# amp1_v0001.net
KiCad netlist of a schematic drawn in EAGLE
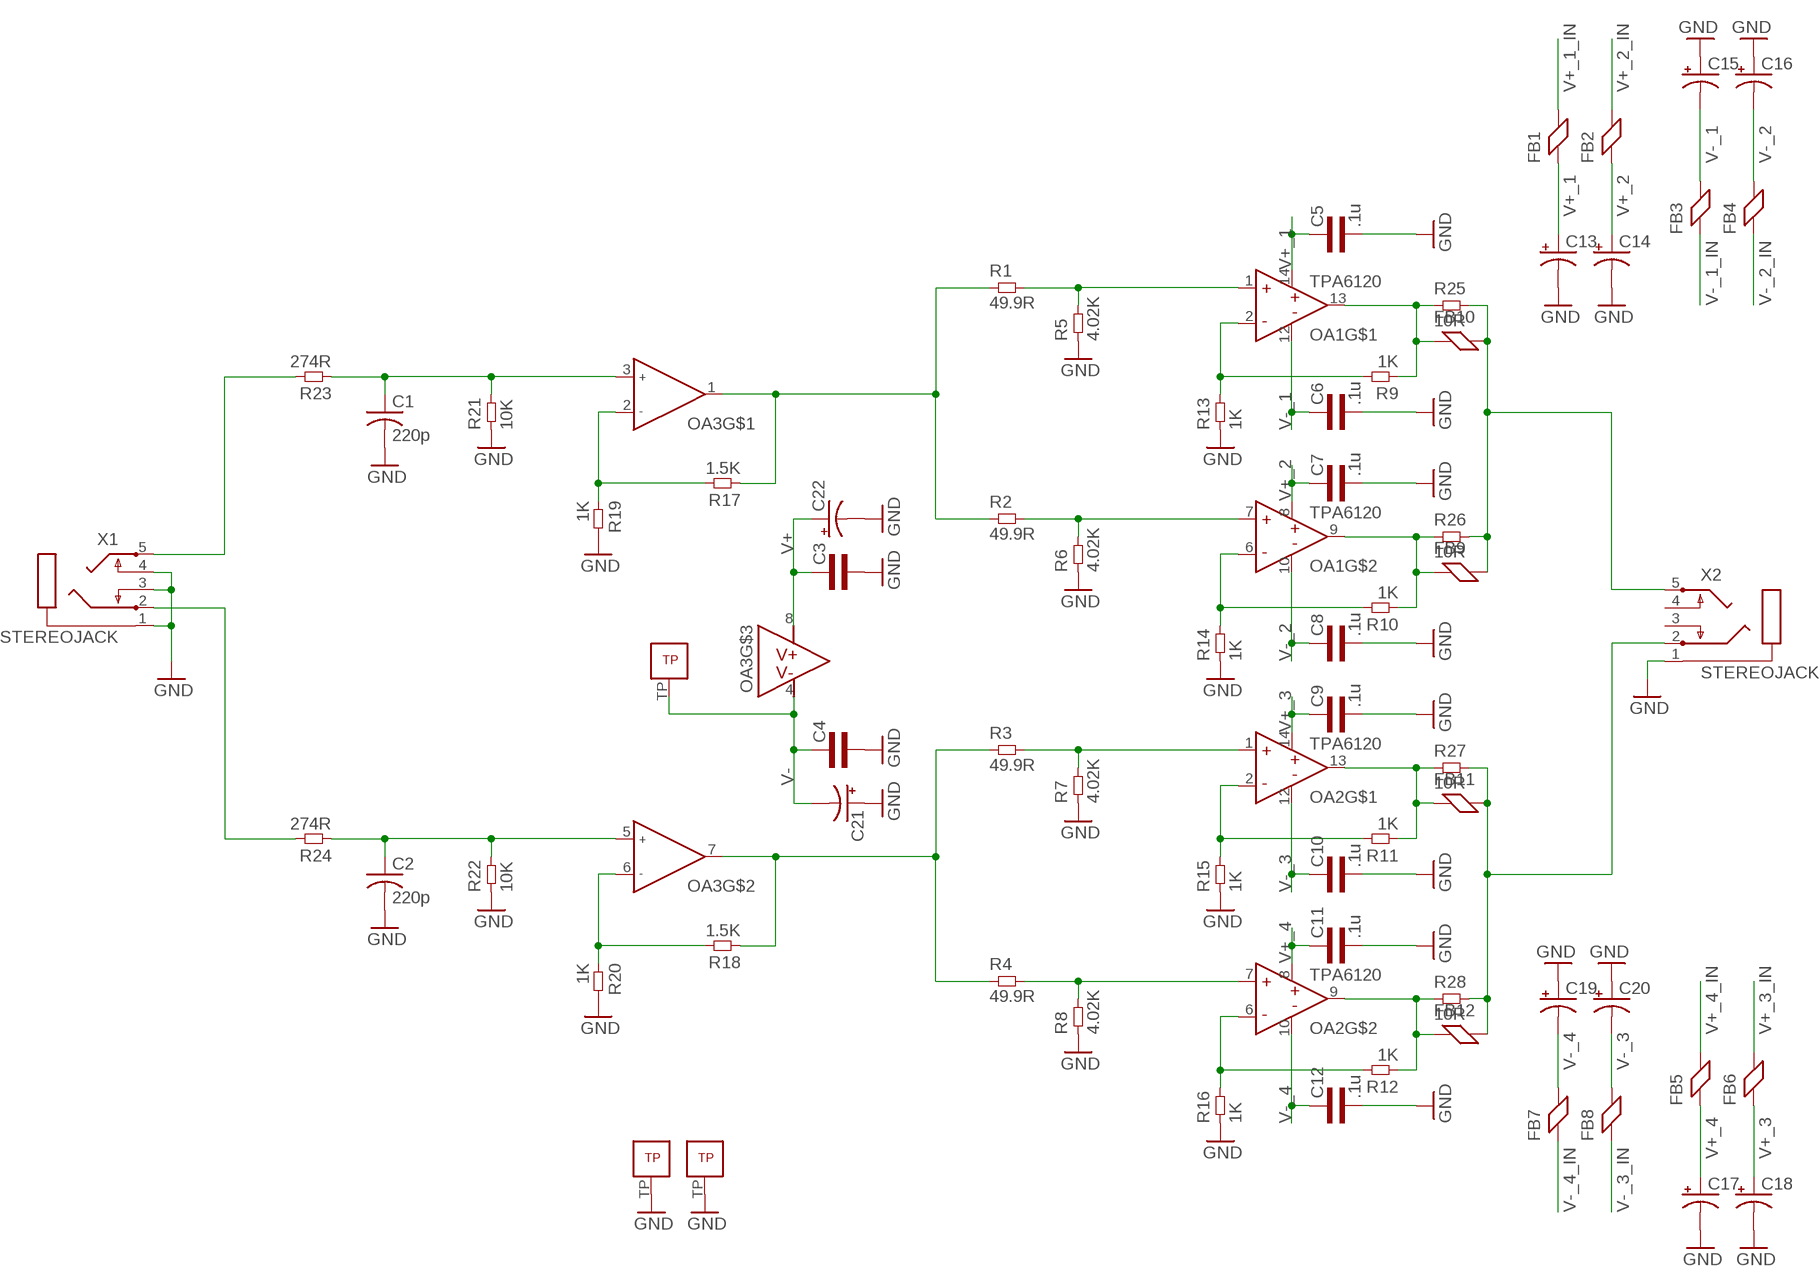
[diagram p0: schematic, sheet 1]

(export (version "E")
  (design (tool "Eeschema 10.0.6"))
  (components
    (comp (ref "C1")
      (value "220p")
      (footprint "eagle-import:C025-025X050")
      (libsource (lib "eagle-import") (part "C-US025-025X050"))
    )
    (comp (ref "C2")
      (value "220p")
      (footprint "eagle-import:C025-025X050")
      (libsource (lib "eagle-import") (part "C-US025-025X050"))
    )
    (comp (ref "C3")
      (value "CAP0603L3")
      (footprint "eagle-import:0603L3")
      (libsource (lib "eagle-import") (part "CAP0603L3"))
    )
    (comp (ref "C4")
      (value "CAP0603L3")
      (footprint "eagle-import:0603L3")
      (libsource (lib "eagle-import") (part "CAP0603L3"))
    )
    (comp (ref "C5")
      (value ".1u")
      (footprint "eagle-import:0603L3")
      (libsource (lib "eagle-import") (part "CAP0603L3"))
    )
    (comp (ref "C6")
      (value ".1u")
      (footprint "eagle-import:0603L3")
      (libsource (lib "eagle-import") (part "CAP0603L3"))
    )
    (comp (ref "C7")
      (value ".1u")
      (footprint "eagle-import:0603L3")
      (libsource (lib "eagle-import") (part "CAP0603L3"))
    )
    (comp (ref "C8")
      (value ".1u")
      (footprint "eagle-import:0603L3")
      (libsource (lib "eagle-import") (part "CAP0603L3"))
    )
    (comp (ref "C9")
      (value ".1u")
      (footprint "eagle-import:0603L3")
      (libsource (lib "eagle-import") (part "CAP0603L3"))
    )
    (comp (ref "C10")
      (value ".1u")
      (footprint "eagle-import:0603L3")
      (libsource (lib "eagle-import") (part "CAP0603L3"))
    )
    (comp (ref "C11")
      (value ".1u")
      (footprint "eagle-import:0603L3")
      (libsource (lib "eagle-import") (part "CAP0603L3"))
    )
    (comp (ref "C12")
      (value ".1u")
      (footprint "eagle-import:0603L3")
      (libsource (lib "eagle-import") (part "CAP0603L3"))
    )
    (comp (ref "C13")
      (value "CPOL-USE2-5")
      (footprint "eagle-import:E2-5")
      (libsource (lib "eagle-import") (part "CPOL-USE2-5"))
    )
    (comp (ref "C14")
      (value "CPOL-USE2-5")
      (footprint "eagle-import:E2-5")
      (libsource (lib "eagle-import") (part "CPOL-USE2-5"))
    )
    (comp (ref "C15")
      (value "CPOL-USE2-5")
      (footprint "eagle-import:E2-5")
      (libsource (lib "eagle-import") (part "CPOL-USE2-5"))
    )
    (comp (ref "C16")
      (value "CPOL-USE2-5")
      (footprint "eagle-import:E2-5")
      (libsource (lib "eagle-import") (part "CPOL-USE2-5"))
    )
    (comp (ref "C17")
      (value "CPOL-USE2-5")
      (footprint "eagle-import:E2-5")
      (libsource (lib "eagle-import") (part "CPOL-USE2-5"))
    )
    (comp (ref "C18")
      (value "CPOL-USE2-5")
      (footprint "eagle-import:E2-5")
      (libsource (lib "eagle-import") (part "CPOL-USE2-5"))
    )
    (comp (ref "C19")
      (value "CPOL-USE2-5")
      (footprint "eagle-import:E2-5")
      (libsource (lib "eagle-import") (part "CPOL-USE2-5"))
    )
    (comp (ref "C20")
      (value "CPOL-USE2-5")
      (footprint "eagle-import:E2-5")
      (libsource (lib "eagle-import") (part "CPOL-USE2-5"))
    )
    (comp (ref "C21")
      (value "CPOL-USE2-5")
      (footprint "eagle-import:E2-5")
      (libsource (lib "eagle-import") (part "CPOL-USE2-5"))
    )
    (comp (ref "C22")
      (value "CPOL-USE2-5")
      (footprint "eagle-import:E2-5")
      (libsource (lib "eagle-import") (part "CPOL-USE2-5"))
    )
    (comp (ref "FB1")
      (value "FERRITE0805L3")
      (footprint "eagle-import:0805L3")
      (libsource (lib "eagle-import") (part "FERRITE0805L3"))
    )
    (comp (ref "FB2")
      (value "FERRITE0805L3")
      (footprint "eagle-import:0805L3")
      (libsource (lib "eagle-import") (part "FERRITE0805L3"))
    )
    (comp (ref "FB3")
      (value "FERRITE0805L3")
      (footprint "eagle-import:0805L3")
      (libsource (lib "eagle-import") (part "FERRITE0805L3"))
    )
    (comp (ref "FB4")
      (value "FERRITE0805L3")
      (footprint "eagle-import:0805L3")
      (libsource (lib "eagle-import") (part "FERRITE0805L3"))
    )
    (comp (ref "FB5")
      (value "FERRITE0805L3")
      (footprint "eagle-import:0805L3")
      (libsource (lib "eagle-import") (part "FERRITE0805L3"))
    )
    (comp (ref "FB6")
      (value "FERRITE0805L3")
      (footprint "eagle-import:0805L3")
      (libsource (lib "eagle-import") (part "FERRITE0805L3"))
    )
    (comp (ref "FB7")
      (value "FERRITE0805L3")
      (footprint "eagle-import:0805L3")
      (libsource (lib "eagle-import") (part "FERRITE0805L3"))
    )
    (comp (ref "FB8")
      (value "FERRITE0805L3")
      (footprint "eagle-import:0805L3")
      (libsource (lib "eagle-import") (part "FERRITE0805L3"))
    )
    (comp (ref "FB9")
      (value "FERRITE0805L3")
      (footprint "eagle-import:0805L3")
      (libsource (lib "eagle-import") (part "FERRITE0805L3"))
    )
    (comp (ref "FB10")
      (value "FERRITE0805L3")
      (footprint "eagle-import:0805L3")
      (libsource (lib "eagle-import") (part "FERRITE0805L3"))
    )
    (comp (ref "FB11")
      (value "FERRITE0805L3")
      (footprint "eagle-import:0805L3")
      (libsource (lib "eagle-import") (part "FERRITE0805L3"))
    )
    (comp (ref "FB12")
      (value "FERRITE0805L3")
      (footprint "eagle-import:0805L3")
      (libsource (lib "eagle-import") (part "FERRITE0805L3"))
    )
    (comp (ref "OA1")
      (value "TPA6120QFN")
      (footprint "eagle-import:S-PVQFN-N14")
      (libsource (lib "eagle-import") (part "TPA6120QFN"))
    )
    (comp (ref "OA2")
      (value "TPA6120QFN")
      (footprint "eagle-import:S-PVQFN-N14")
      (libsource (lib "eagle-import") (part "TPA6120QFN"))
    )
    (comp (ref "OA3")
      (value "OPA1612")
      (footprint "eagle-import:S-PWSON-N8")
      (libsource (lib "eagle-import") (part "OPA1612"))
    )
    (comp (ref "R1")
      (value "49.9R")
      (footprint "eagle-import:0805L3")
      (libsource (lib "eagle-import") (part "RES0805L3"))
    )
    (comp (ref "R2")
      (value "49.9R")
      (footprint "eagle-import:0805L3")
      (libsource (lib "eagle-import") (part "RES0805L3"))
    )
    (comp (ref "R3")
      (value "49.9R")
      (footprint "eagle-import:0805L3")
      (libsource (lib "eagle-import") (part "RES0805L3"))
    )
    (comp (ref "R4")
      (value "49.9R")
      (footprint "eagle-import:0805L3")
      (libsource (lib "eagle-import") (part "RES0805L3"))
    )
    (comp (ref "R5")
      (value "4.02K")
      (footprint "eagle-import:0805L3")
      (libsource (lib "eagle-import") (part "RES0805L3"))
    )
    (comp (ref "R6")
      (value "4.02K")
      (footprint "eagle-import:0805L3")
      (libsource (lib "eagle-import") (part "RES0805L3"))
    )
    (comp (ref "R7")
      (value "4.02K")
      (footprint "eagle-import:0805L3")
      (libsource (lib "eagle-import") (part "RES0805L3"))
    )
    (comp (ref "R8")
      (value "4.02K")
      (footprint "eagle-import:0805L3")
      (libsource (lib "eagle-import") (part "RES0805L3"))
    )
    (comp (ref "R9")
      (value "1K")
      (footprint "eagle-import:0805L3")
      (libsource (lib "eagle-import") (part "RES0805L3"))
    )
    (comp (ref "R10")
      (value "1K")
      (footprint "eagle-import:0805L3")
      (libsource (lib "eagle-import") (part "RES0805L3"))
    )
    (comp (ref "R11")
      (value "1K")
      (footprint "eagle-import:0805L3")
      (libsource (lib "eagle-import") (part "RES0805L3"))
    )
    (comp (ref "R12")
      (value "1K")
      (footprint "eagle-import:0805L3")
      (libsource (lib "eagle-import") (part "RES0805L3"))
    )
    (comp (ref "R13")
      (value "1K")
      (footprint "eagle-import:0805L3")
      (libsource (lib "eagle-import") (part "RES0805L3"))
    )
    (comp (ref "R14")
      (value "1K")
      (footprint "eagle-import:0805L3")
      (libsource (lib "eagle-import") (part "RES0805L3"))
    )
    (comp (ref "R15")
      (value "1K")
      (footprint "eagle-import:0805L3")
      (libsource (lib "eagle-import") (part "RES0805L3"))
    )
    (comp (ref "R16")
      (value "1K")
      (footprint "eagle-import:0805L3")
      (libsource (lib "eagle-import") (part "RES0805L3"))
    )
    (comp (ref "R17")
      (value "1.5K")
      (footprint "eagle-import:0805L3")
      (libsource (lib "eagle-import") (part "RES0805L3"))
    )
    (comp (ref "R18")
      (value "1.5K")
      (footprint "eagle-import:0805L3")
      (libsource (lib "eagle-import") (part "RES0805L3"))
    )
    (comp (ref "R19")
      (value "1K")
      (footprint "eagle-import:0805L3")
      (libsource (lib "eagle-import") (part "RES0805L3"))
    )
    (comp (ref "R20")
      (value "1K")
      (footprint "eagle-import:0805L3")
      (libsource (lib "eagle-import") (part "RES0805L3"))
    )
    (comp (ref "R21")
      (value "10K")
      (footprint "eagle-import:0805L3")
      (libsource (lib "eagle-import") (part "RES0805L3"))
    )
    (comp (ref "R22")
      (value "10K")
      (footprint "eagle-import:0805L3")
      (libsource (lib "eagle-import") (part "RES0805L3"))
    )
    (comp (ref "R23")
      (value "274R")
      (footprint "eagle-import:0805L3")
      (libsource (lib "eagle-import") (part "RES0805L3"))
    )
    (comp (ref "R24")
      (value "274R")
      (footprint "eagle-import:0805L3")
      (libsource (lib "eagle-import") (part "RES0805L3"))
    )
    (comp (ref "R25")
      (value "10R")
      (footprint "eagle-import:1206L3")
      (libsource (lib "eagle-import") (part "RES1206L3"))
    )
    (comp (ref "R26")
      (value "10R")
      (footprint "eagle-import:1206L3")
      (libsource (lib "eagle-import") (part "RES1206L3"))
    )
    (comp (ref "R27")
      (value "10R")
      (footprint "eagle-import:1206L3")
      (libsource (lib "eagle-import") (part "RES1206L3"))
    )
    (comp (ref "R28")
      (value "10R")
      (footprint "eagle-import:1206L3")
      (libsource (lib "eagle-import") (part "RES1206L3"))
    )
    (comp (ref "X1")
      (value "STEREOJACK")
      (footprint "eagle-import:STX3100")
      (libsource (lib "eagle-import") (part "STEREOJACK"))
    )
    (comp (ref "X2")
      (value "STEREOJACK")
      (footprint "eagle-import:STX3100")
      (libsource (lib "eagle-import") (part "STEREOJACK"))
    )
  )
  (nets
    (net (code "1") (name "/V+") (class "Default")
      (node (ref "C22") (pin "+") (pinfunction "+_+") (pintype "passive"))
      (node (ref "C3") (pin "P$1") (pinfunction "1_P$1") (pintype "bidirectional"))
      (node (ref "OA3") (pin "8") (pinfunction "V+_8") (pintype "power_in"))
    )
    (net (code "2") (name "/V+_1") (class "Default")
      (node (ref "C13") (pin "+") (pinfunction "+_+") (pintype "passive"))
      (node (ref "C5") (pin "P$1") (pinfunction "1_P$1") (pintype "bidirectional"))
      (node (ref "FB1") (pin "1") (pinfunction "1_1") (pintype "bidirectional"))
      (node (ref "OA1") (pin "14") (pinfunction "V+_14") (pintype "bidirectional"))
    )
    (net (code "3") (name "/V+_1_IN") (class "Default")
      (node (ref "FB1") (pin "2") (pinfunction "2_2") (pintype "bidirectional"))
    )
    (net (code "4") (name "/V+_2") (class "Default")
      (node (ref "C14") (pin "+") (pinfunction "+_+") (pintype "passive"))
      (node (ref "C7") (pin "P$1") (pinfunction "1_P$1") (pintype "bidirectional"))
      (node (ref "FB2") (pin "1") (pinfunction "1_1") (pintype "bidirectional"))
      (node (ref "OA1") (pin "8") (pinfunction "V+_8") (pintype "bidirectional"))
    )
    (net (code "5") (name "/V+_2_IN") (class "Default")
      (node (ref "FB2") (pin "2") (pinfunction "2_2") (pintype "bidirectional"))
    )
    (net (code "6") (name "/V+_3") (class "Default")
      (node (ref "C18") (pin "+") (pinfunction "+_+") (pintype "passive"))
      (node (ref "C9") (pin "P$1") (pinfunction "1_P$1") (pintype "bidirectional"))
      (node (ref "FB6") (pin "1") (pinfunction "1_1") (pintype "bidirectional"))
      (node (ref "OA2") (pin "14") (pinfunction "V+_14") (pintype "bidirectional"))
    )
    (net (code "7") (name "/V+_3_IN") (class "Default")
      (node (ref "FB6") (pin "2") (pinfunction "2_2") (pintype "bidirectional"))
    )
    (net (code "8") (name "/V+_4") (class "Default")
      (node (ref "C11") (pin "P$1") (pinfunction "1_P$1") (pintype "bidirectional"))
      (node (ref "C17") (pin "+") (pinfunction "+_+") (pintype "passive"))
      (node (ref "FB5") (pin "1") (pinfunction "1_1") (pintype "bidirectional"))
      (node (ref "OA2") (pin "8") (pinfunction "V+_8") (pintype "bidirectional"))
    )
    (net (code "9") (name "/V+_4_IN") (class "Default")
      (node (ref "FB5") (pin "2") (pinfunction "2_2") (pintype "bidirectional"))
    )
    (net (code "10") (name "/V-") (class "Default")
      (node (ref "C21") (pin "-") (pinfunction "-_-") (pintype "passive"))
      (node (ref "C4") (pin "P$1") (pinfunction "1_P$1") (pintype "bidirectional"))
      (node (ref "OA3") (pin "4") (pinfunction "V-_4") (pintype "power_in"))
      (node (ref "OA3") (pin "TP") (pinfunction "TP_TP") (pintype "bidirectional"))
    )
    (net (code "11") (name "/V-_1") (class "Default")
      (node (ref "C15") (pin "-") (pinfunction "-_-") (pintype "passive"))
      (node (ref "C6") (pin "P$1") (pinfunction "1_P$1") (pintype "bidirectional"))
      (node (ref "FB3") (pin "2") (pinfunction "2_2") (pintype "bidirectional"))
      (node (ref "OA1") (pin "12") (pinfunction "V-_12") (pintype "bidirectional"))
    )
    (net (code "12") (name "/V-_1_IN") (class "Default")
      (node (ref "FB3") (pin "1") (pinfunction "1_1") (pintype "bidirectional"))
    )
    (net (code "13") (name "/V-_2") (class "Default")
      (node (ref "C16") (pin "-") (pinfunction "-_-") (pintype "passive"))
      (node (ref "C8") (pin "P$1") (pinfunction "1_P$1") (pintype "bidirectional"))
      (node (ref "FB4") (pin "2") (pinfunction "2_2") (pintype "bidirectional"))
      (node (ref "OA1") (pin "10") (pinfunction "V-_10") (pintype "bidirectional"))
    )
    (net (code "14") (name "/V-_2_IN") (class "Default")
      (node (ref "FB4") (pin "1") (pinfunction "1_1") (pintype "bidirectional"))
    )
    (net (code "15") (name "/V-_3") (class "Default")
      (node (ref "C10") (pin "P$1") (pinfunction "1_P$1") (pintype "bidirectional"))
      (node (ref "C20") (pin "-") (pinfunction "-_-") (pintype "passive"))
      (node (ref "FB8") (pin "2") (pinfunction "2_2") (pintype "bidirectional"))
      (node (ref "OA2") (pin "12") (pinfunction "V-_12") (pintype "bidirectional"))
    )
    (net (code "16") (name "/V-_3_IN") (class "Default")
      (node (ref "FB8") (pin "1") (pinfunction "1_1") (pintype "bidirectional"))
    )
    (net (code "17") (name "/V-_4") (class "Default")
      (node (ref "C12") (pin "P$1") (pinfunction "1_P$1") (pintype "bidirectional"))
      (node (ref "C19") (pin "-") (pinfunction "-_-") (pintype "passive"))
      (node (ref "FB7") (pin "2") (pinfunction "2_2") (pintype "bidirectional"))
      (node (ref "OA2") (pin "10") (pinfunction "V-_10") (pintype "bidirectional"))
    )
    (net (code "18") (name "/V-_4_IN") (class "Default")
      (node (ref "FB7") (pin "1") (pinfunction "1_1") (pintype "bidirectional"))
    )
    (net (code "19") (name "GND") (class "Default")
      (node (ref "C1") (pin "2") (pinfunction "2_2") (pintype "passive"))
      (node (ref "C10") (pin "P$2") (pinfunction "2_P$2") (pintype "bidirectional"))
      (node (ref "C11") (pin "P$2") (pinfunction "2_P$2") (pintype "bidirectional"))
      (node (ref "C12") (pin "P$2") (pinfunction "2_P$2") (pintype "bidirectional"))
      (node (ref "C13") (pin "-") (pinfunction "-_-") (pintype "passive"))
      (node (ref "C14") (pin "-") (pinfunction "-_-") (pintype "passive"))
      (node (ref "C15") (pin "+") (pinfunction "+_+") (pintype "passive"))
      (node (ref "C16") (pin "+") (pinfunction "+_+") (pintype "passive"))
      (node (ref "C17") (pin "-") (pinfunction "-_-") (pintype "passive"))
      (node (ref "C18") (pin "-") (pinfunction "-_-") (pintype "passive"))
      (node (ref "C19") (pin "+") (pinfunction "+_+") (pintype "passive"))
      (node (ref "C2") (pin "2") (pinfunction "2_2") (pintype "passive"))
      (node (ref "C20") (pin "+") (pinfunction "+_+") (pintype "passive"))
      (node (ref "C21") (pin "+") (pinfunction "+_+") (pintype "passive"))
      (node (ref "C22") (pin "-") (pinfunction "-_-") (pintype "passive"))
      (node (ref "C3") (pin "P$2") (pinfunction "2_P$2") (pintype "bidirectional"))
      (node (ref "C4") (pin "P$2") (pinfunction "2_P$2") (pintype "bidirectional"))
      (node (ref "C5") (pin "P$2") (pinfunction "2_P$2") (pintype "bidirectional"))
      (node (ref "C6") (pin "P$2") (pinfunction "2_P$2") (pintype "bidirectional"))
      (node (ref "C7") (pin "P$2") (pinfunction "2_P$2") (pintype "bidirectional"))
      (node (ref "C8") (pin "P$2") (pinfunction "2_P$2") (pintype "bidirectional"))
      (node (ref "C9") (pin "P$2") (pinfunction "2_P$2") (pintype "bidirectional"))
      (node (ref "OA1") (pin "TP") (pinfunction "TP_TP") (pintype "bidirectional"))
      (node (ref "OA2") (pin "TP") (pinfunction "TP_TP") (pintype "bidirectional"))
      (node (ref "R13") (pin "1") (pinfunction "1_1") (pintype "bidirectional"))
      (node (ref "R14") (pin "1") (pinfunction "1_1") (pintype "bidirectional"))
      (node (ref "R15") (pin "1") (pinfunction "1_1") (pintype "bidirectional"))
      (node (ref "R16") (pin "1") (pinfunction "1_1") (pintype "bidirectional"))
      (node (ref "R19") (pin "2") (pinfunction "2_2") (pintype "bidirectional"))
      (node (ref "R20") (pin "2") (pinfunction "2_2") (pintype "bidirectional"))
      (node (ref "R21") (pin "1") (pinfunction "1_1") (pintype "bidirectional"))
      (node (ref "R22") (pin "1") (pinfunction "1_1") (pintype "bidirectional"))
      (node (ref "R5") (pin "1") (pinfunction "1_1") (pintype "bidirectional"))
      (node (ref "R6") (pin "1") (pinfunction "1_1") (pintype "bidirectional"))
      (node (ref "R7") (pin "1") (pinfunction "1_1") (pintype "bidirectional"))
      (node (ref "R8") (pin "1") (pinfunction "1_1") (pintype "bidirectional"))
      (node (ref "X1") (pin "1") (pinfunction "1_1") (pintype "passive"))
      (node (ref "X1") (pin "3") (pinfunction "3_3") (pintype "passive"))
      (node (ref "X1") (pin "4") (pinfunction "4_4") (pintype "passive"))
      (node (ref "X2") (pin "1") (pinfunction "1_1") (pintype "passive"))
    )
    (net (code "20") (name "Net-(FB10-Pad2)") (class "Default")
      (node (ref "FB10") (pin "2") (pinfunction "2_2") (pintype "bidirectional"))
      (node (ref "FB9") (pin "2") (pinfunction "2_2") (pintype "bidirectional"))
      (node (ref "R25") (pin "2") (pinfunction "2_2") (pintype "bidirectional"))
      (node (ref "R26") (pin "2") (pinfunction "2_2") (pintype "bidirectional"))
      (node (ref "X2") (pin "5") (pinfunction "5_5") (pintype "passive"))
    )
    (net (code "21") (name "Net-(FB11-Pad2)") (class "Default")
      (node (ref "FB11") (pin "2") (pinfunction "2_2") (pintype "bidirectional"))
      (node (ref "FB12") (pin "2") (pinfunction "2_2") (pintype "bidirectional"))
      (node (ref "R27") (pin "2") (pinfunction "2_2") (pintype "bidirectional"))
      (node (ref "R28") (pin "2") (pinfunction "2_2") (pintype "bidirectional"))
      (node (ref "X2") (pin "2") (pinfunction "2_2") (pintype "passive"))
    )
    (net (code "22") (name "Net-(OA1A-IN+)") (class "Default")
      (node (ref "OA1") (pin "1") (pinfunction "IN+_1") (pintype "bidirectional"))
      (node (ref "R1") (pin "2") (pinfunction "2_2") (pintype "bidirectional"))
      (node (ref "R5") (pin "2") (pinfunction "2_2") (pintype "bidirectional"))
    )
    (net (code "23") (name "Net-(OA1A-IN-)") (class "Default")
      (node (ref "OA1") (pin "2") (pinfunction "IN-_2") (pintype "bidirectional"))
      (node (ref "R13") (pin "2") (pinfunction "2_2") (pintype "bidirectional"))
      (node (ref "R9") (pin "2") (pinfunction "2_2") (pintype "bidirectional"))
    )
    (net (code "24") (name "Net-(OA1A-OUT)") (class "Default")
      (node (ref "FB10") (pin "1") (pinfunction "1_1") (pintype "bidirectional"))
      (node (ref "OA1") (pin "13") (pinfunction "OUT_13") (pintype "bidirectional"))
      (node (ref "R25") (pin "1") (pinfunction "1_1") (pintype "bidirectional"))
      (node (ref "R9") (pin "1") (pinfunction "1_1") (pintype "bidirectional"))
    )
    (net (code "25") (name "Net-(OA1B-IN+)") (class "Default")
      (node (ref "OA1") (pin "7") (pinfunction "IN+_7") (pintype "bidirectional"))
      (node (ref "R2") (pin "2") (pinfunction "2_2") (pintype "bidirectional"))
      (node (ref "R6") (pin "2") (pinfunction "2_2") (pintype "bidirectional"))
    )
    (net (code "26") (name "Net-(OA1B-IN-)") (class "Default")
      (node (ref "OA1") (pin "6") (pinfunction "IN-_6") (pintype "bidirectional"))
      (node (ref "R10") (pin "2") (pinfunction "2_2") (pintype "bidirectional"))
      (node (ref "R14") (pin "2") (pinfunction "2_2") (pintype "bidirectional"))
    )
    (net (code "27") (name "Net-(OA1B-OUT)") (class "Default")
      (node (ref "FB9") (pin "1") (pinfunction "1_1") (pintype "bidirectional"))
      (node (ref "OA1") (pin "9") (pinfunction "OUT_9") (pintype "bidirectional"))
      (node (ref "R10") (pin "1") (pinfunction "1_1") (pintype "bidirectional"))
      (node (ref "R26") (pin "1") (pinfunction "1_1") (pintype "bidirectional"))
    )
    (net (code "28") (name "Net-(OA2A-IN+)") (class "Default")
      (node (ref "OA2") (pin "1") (pinfunction "IN+_1") (pintype "bidirectional"))
      (node (ref "R3") (pin "2") (pinfunction "2_2") (pintype "bidirectional"))
      (node (ref "R7") (pin "2") (pinfunction "2_2") (pintype "bidirectional"))
    )
    (net (code "29") (name "Net-(OA2A-IN-)") (class "Default")
      (node (ref "OA2") (pin "2") (pinfunction "IN-_2") (pintype "bidirectional"))
      (node (ref "R11") (pin "2") (pinfunction "2_2") (pintype "bidirectional"))
      (node (ref "R15") (pin "2") (pinfunction "2_2") (pintype "bidirectional"))
    )
    (net (code "30") (name "Net-(OA2A-OUT)") (class "Default")
      (node (ref "FB11") (pin "1") (pinfunction "1_1") (pintype "bidirectional"))
      (node (ref "OA2") (pin "13") (pinfunction "OUT_13") (pintype "bidirectional"))
      (node (ref "R11") (pin "1") (pinfunction "1_1") (pintype "bidirectional"))
      (node (ref "R27") (pin "1") (pinfunction "1_1") (pintype "bidirectional"))
    )
    (net (code "31") (name "Net-(OA2B-IN+)") (class "Default")
      (node (ref "OA2") (pin "7") (pinfunction "IN+_7") (pintype "bidirectional"))
      (node (ref "R4") (pin "2") (pinfunction "2_2") (pintype "bidirectional"))
      (node (ref "R8") (pin "2") (pinfunction "2_2") (pintype "bidirectional"))
    )
    (net (code "32") (name "Net-(OA2B-IN-)") (class "Default")
      (node (ref "OA2") (pin "6") (pinfunction "IN-_6") (pintype "bidirectional"))
      (node (ref "R12") (pin "2") (pinfunction "2_2") (pintype "bidirectional"))
      (node (ref "R16") (pin "2") (pinfunction "2_2") (pintype "bidirectional"))
    )
    (net (code "33") (name "Net-(OA2B-OUT)") (class "Default")
      (node (ref "FB12") (pin "1") (pinfunction "1_1") (pintype "bidirectional"))
      (node (ref "OA2") (pin "9") (pinfunction "OUT_9") (pintype "bidirectional"))
      (node (ref "R12") (pin "1") (pinfunction "1_1") (pintype "bidirectional"))
      (node (ref "R28") (pin "1") (pinfunction "1_1") (pintype "bidirectional"))
    )
    (net (code "34") (name "Net-(OA3A-INA+)") (class "Default")
      (node (ref "C1") (pin "1") (pinfunction "1_1") (pintype "passive"))
      (node (ref "OA3") (pin "3") (pinfunction "INA+_3") (pintype "bidirectional"))
      (node (ref "R21") (pin "2") (pinfunction "2_2") (pintype "bidirectional"))
      (node (ref "R23") (pin "1") (pinfunction "1_1") (pintype "bidirectional"))
    )
    (net (code "35") (name "Net-(OA3A-INA-)") (class "Default")
      (node (ref "OA3") (pin "2") (pinfunction "INA-_2") (pintype "bidirectional"))
      (node (ref "R17") (pin "2") (pinfunction "2_2") (pintype "bidirectional"))
      (node (ref "R19") (pin "1") (pinfunction "1_1") (pintype "bidirectional"))
    )
    (net (code "36") (name "Net-(OA3A-OUTA)") (class "Default")
      (node (ref "OA3") (pin "1") (pinfunction "OUTA_1") (pintype "bidirectional"))
      (node (ref "R1") (pin "1") (pinfunction "1_1") (pintype "bidirectional"))
      (node (ref "R17") (pin "1") (pinfunction "1_1") (pintype "bidirectional"))
      (node (ref "R2") (pin "1") (pinfunction "1_1") (pintype "bidirectional"))
    )
    (net (code "37") (name "Net-(OA3B-INB+)") (class "Default")
      (node (ref "C2") (pin "1") (pinfunction "1_1") (pintype "passive"))
      (node (ref "OA3") (pin "5") (pinfunction "INB+_5") (pintype "bidirectional"))
      (node (ref "R22") (pin "2") (pinfunction "2_2") (pintype "bidirectional"))
      (node (ref "R24") (pin "1") (pinfunction "1_1") (pintype "bidirectional"))
    )
    (net (code "38") (name "Net-(OA3B-INB-)") (class "Default")
      (node (ref "OA3") (pin "6") (pinfunction "INB-_6") (pintype "bidirectional"))
      (node (ref "R18") (pin "2") (pinfunction "2_2") (pintype "bidirectional"))
      (node (ref "R20") (pin "1") (pinfunction "1_1") (pintype "bidirectional"))
    )
    (net (code "39") (name "Net-(OA3B-OUTB)") (class "Default")
      (node (ref "OA3") (pin "7") (pinfunction "OUTB_7") (pintype "bidirectional"))
      (node (ref "R18") (pin "1") (pinfunction "1_1") (pintype "bidirectional"))
      (node (ref "R3") (pin "1") (pinfunction "1_1") (pintype "bidirectional"))
      (node (ref "R4") (pin "1") (pinfunction "1_1") (pintype "bidirectional"))
    )
    (net (code "40") (name "Net-(R23-Pad2)") (class "Default")
      (node (ref "R23") (pin "2") (pinfunction "2_2") (pintype "bidirectional"))
      (node (ref "X1") (pin "5") (pinfunction "5_5") (pintype "passive"))
    )
    (net (code "41") (name "Net-(R24-Pad2)") (class "Default")
      (node (ref "R24") (pin "2") (pinfunction "2_2") (pintype "bidirectional"))
      (node (ref "X1") (pin "2") (pinfunction "2_2") (pintype "passive"))
    )
    (net (code "42") (name "unconnected-(X2-Pad3)") (class "Default")
      (node (ref "X2") (pin "3") (pinfunction "3_3") (pintype "passive"))
    )
    (net (code "43") (name "unconnected-(X2-Pad4)") (class "Default")
      (node (ref "X2") (pin "4") (pinfunction "4_4") (pintype "passive"))
    )
  )
)
